# Monitor_strip_5050.net
KiCad netlist of a schematic drawn in EAGLE
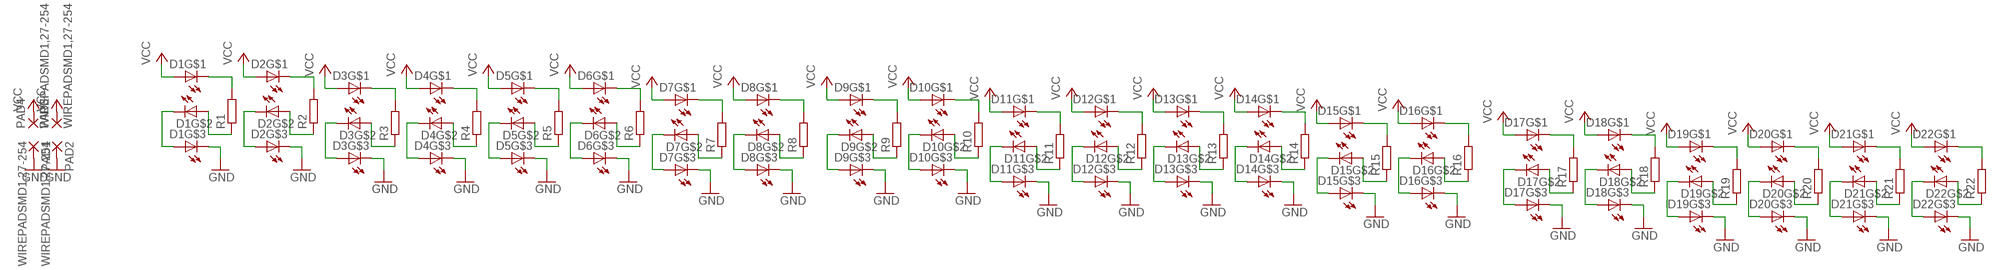
[diagram p0: schematic, sheet 1]

(export (version "E")
  (design (tool "Eeschema 10.0.6"))
  (components
    (comp (ref "D1")
      (value "LED5050_SEPARATES")
      (footprint "eagle-import:LED505_SMALLPADS")
      (libsource (lib "eagle-import") (part "LED5050_SEPARATES"))
    )
    (comp (ref "D2")
      (value "LED5050_SEPARATES")
      (footprint "eagle-import:LED505_SMALLPADS")
      (libsource (lib "eagle-import") (part "LED5050_SEPARATES"))
    )
    (comp (ref "D3")
      (value "LED5050_SEPARATES")
      (footprint "eagle-import:LED505_SMALLPADS")
      (libsource (lib "eagle-import") (part "LED5050_SEPARATES"))
    )
    (comp (ref "D4")
      (value "LED5050_SEPARATES")
      (footprint "eagle-import:LED505_SMALLPADS")
      (libsource (lib "eagle-import") (part "LED5050_SEPARATES"))
    )
    (comp (ref "D5")
      (value "LED5050_SEPARATES")
      (footprint "eagle-import:LED505_SMALLPADS")
      (libsource (lib "eagle-import") (part "LED5050_SEPARATES"))
    )
    (comp (ref "D6")
      (value "LED5050_SEPARATES")
      (footprint "eagle-import:LED505_SMALLPADS")
      (libsource (lib "eagle-import") (part "LED5050_SEPARATES"))
    )
    (comp (ref "D7")
      (value "LED5050_SEPARATES")
      (footprint "eagle-import:LED505_SMALLPADS")
      (libsource (lib "eagle-import") (part "LED5050_SEPARATES"))
    )
    (comp (ref "D8")
      (value "LED5050_SEPARATES")
      (footprint "eagle-import:LED505_SMALLPADS")
      (libsource (lib "eagle-import") (part "LED5050_SEPARATES"))
    )
    (comp (ref "D9")
      (value "LED5050_SEPARATES")
      (footprint "eagle-import:LED505_SMALLPADS")
      (libsource (lib "eagle-import") (part "LED5050_SEPARATES"))
    )
    (comp (ref "D10")
      (value "LED5050_SEPARATES")
      (footprint "eagle-import:LED505_SMALLPADS")
      (libsource (lib "eagle-import") (part "LED5050_SEPARATES"))
    )
    (comp (ref "D11")
      (value "LED5050_SEPARATES")
      (footprint "eagle-import:LED505_SMALLPADS")
      (libsource (lib "eagle-import") (part "LED5050_SEPARATES"))
    )
    (comp (ref "D12")
      (value "LED5050_SEPARATES")
      (footprint "eagle-import:LED505_SMALLPADS")
      (libsource (lib "eagle-import") (part "LED5050_SEPARATES"))
    )
    (comp (ref "D13")
      (value "LED5050_SEPARATES")
      (footprint "eagle-import:LED505_SMALLPADS")
      (libsource (lib "eagle-import") (part "LED5050_SEPARATES"))
    )
    (comp (ref "D14")
      (value "LED5050_SEPARATES")
      (footprint "eagle-import:LED505_SMALLPADS")
      (libsource (lib "eagle-import") (part "LED5050_SEPARATES"))
    )
    (comp (ref "D15")
      (value "LED5050_SEPARATES")
      (footprint "eagle-import:LED505_SMALLPADS")
      (libsource (lib "eagle-import") (part "LED5050_SEPARATES"))
    )
    (comp (ref "D16")
      (value "LED5050_SEPARATES")
      (footprint "eagle-import:LED505_SMALLPADS")
      (libsource (lib "eagle-import") (part "LED5050_SEPARATES"))
    )
    (comp (ref "D17")
      (value "LED5050_SEPARATES")
      (footprint "eagle-import:LED505_SMALLPADS")
      (libsource (lib "eagle-import") (part "LED5050_SEPARATES"))
    )
    (comp (ref "D18")
      (value "LED5050_SEPARATES")
      (footprint "eagle-import:LED505_SMALLPADS")
      (libsource (lib "eagle-import") (part "LED5050_SEPARATES"))
    )
    (comp (ref "D19")
      (value "LED5050_SEPARATES")
      (footprint "eagle-import:LED505_SMALLPADS")
      (libsource (lib "eagle-import") (part "LED5050_SEPARATES"))
    )
    (comp (ref "D20")
      (value "LED5050_SEPARATES")
      (footprint "eagle-import:LED505_SMALLPADS")
      (libsource (lib "eagle-import") (part "LED5050_SEPARATES"))
    )
    (comp (ref "D21")
      (value "LED5050_SEPARATES")
      (footprint "eagle-import:LED505_SMALLPADS")
      (libsource (lib "eagle-import") (part "LED5050_SEPARATES"))
    )
    (comp (ref "D22")
      (value "LED5050_SEPARATES")
      (footprint "eagle-import:LED505_SMALLPADS")
      (libsource (lib "eagle-import") (part "LED5050_SEPARATES"))
    )
    (comp (ref "PAD1")
      (value "WIREPADSMD1,27-254")
      (footprint "eagle-import:SMD1,27-2,54")
      (libsource (lib "eagle-import") (part "WIREPADSMD1,27-254"))
    )
    (comp (ref "PAD2")
      (value "WIREPADSMD1,27-254")
      (footprint "eagle-import:SMD1,27-2,54")
      (libsource (lib "eagle-import") (part "WIREPADSMD1,27-254"))
    )
    (comp (ref "PAD3")
      (value "WIREPADSMD1,27-254")
      (footprint "eagle-import:SMD1,27-2,54")
      (libsource (lib "eagle-import") (part "WIREPADSMD1,27-254"))
    )
    (comp (ref "PAD4")
      (value "WIREPADSMD1,27-254")
      (footprint "eagle-import:SMD1,27-2,54")
      (libsource (lib "eagle-import") (part "WIREPADSMD1,27-254"))
    )
    (comp (ref "R1")
      (value "R-EU_R0805")
      (footprint "eagle-import:R0805")
      (libsource (lib "eagle-import") (part "R-EU_R0805"))
    )
    (comp (ref "R2")
      (value "R-EU_R0805")
      (footprint "eagle-import:R0805")
      (libsource (lib "eagle-import") (part "R-EU_R0805"))
    )
    (comp (ref "R3")
      (value "R-EU_R0805")
      (footprint "eagle-import:R0805")
      (libsource (lib "eagle-import") (part "R-EU_R0805"))
    )
    (comp (ref "R4")
      (value "R-EU_R0805")
      (footprint "eagle-import:R0805")
      (libsource (lib "eagle-import") (part "R-EU_R0805"))
    )
    (comp (ref "R5")
      (value "R-EU_R0805")
      (footprint "eagle-import:R0805")
      (libsource (lib "eagle-import") (part "R-EU_R0805"))
    )
    (comp (ref "R6")
      (value "R-EU_R0805")
      (footprint "eagle-import:R0805")
      (libsource (lib "eagle-import") (part "R-EU_R0805"))
    )
    (comp (ref "R7")
      (value "R-EU_R0805")
      (footprint "eagle-import:R0805")
      (libsource (lib "eagle-import") (part "R-EU_R0805"))
    )
    (comp (ref "R8")
      (value "R-EU_R0805")
      (footprint "eagle-import:R0805")
      (libsource (lib "eagle-import") (part "R-EU_R0805"))
    )
    (comp (ref "R9")
      (value "R-EU_R0805")
      (footprint "eagle-import:R0805")
      (libsource (lib "eagle-import") (part "R-EU_R0805"))
    )
    (comp (ref "R10")
      (value "R-EU_R0805")
      (footprint "eagle-import:R0805")
      (libsource (lib "eagle-import") (part "R-EU_R0805"))
    )
    (comp (ref "R11")
      (value "R-EU_R0805")
      (footprint "eagle-import:R0805")
      (libsource (lib "eagle-import") (part "R-EU_R0805"))
    )
    (comp (ref "R12")
      (value "R-EU_R0805")
      (footprint "eagle-import:R0805")
      (libsource (lib "eagle-import") (part "R-EU_R0805"))
    )
    (comp (ref "R13")
      (value "R-EU_R0805")
      (footprint "eagle-import:R0805")
      (libsource (lib "eagle-import") (part "R-EU_R0805"))
    )
    (comp (ref "R14")
      (value "R-EU_R0805")
      (footprint "eagle-import:R0805")
      (libsource (lib "eagle-import") (part "R-EU_R0805"))
    )
    (comp (ref "R15")
      (value "R-EU_R0805")
      (footprint "eagle-import:R0805")
      (libsource (lib "eagle-import") (part "R-EU_R0805"))
    )
    (comp (ref "R16")
      (value "R-EU_R0805")
      (footprint "eagle-import:R0805")
      (libsource (lib "eagle-import") (part "R-EU_R0805"))
    )
    (comp (ref "R17")
      (value "R-EU_R0805")
      (footprint "eagle-import:R0805")
      (libsource (lib "eagle-import") (part "R-EU_R0805"))
    )
    (comp (ref "R18")
      (value "R-EU_R0805")
      (footprint "eagle-import:R0805")
      (libsource (lib "eagle-import") (part "R-EU_R0805"))
    )
    (comp (ref "R19")
      (value "R-EU_R0805")
      (footprint "eagle-import:R0805")
      (libsource (lib "eagle-import") (part "R-EU_R0805"))
    )
    (comp (ref "R20")
      (value "R-EU_R0805")
      (footprint "eagle-import:R0805")
      (libsource (lib "eagle-import") (part "R-EU_R0805"))
    )
    (comp (ref "R21")
      (value "R-EU_R0805")
      (footprint "eagle-import:R0805")
      (libsource (lib "eagle-import") (part "R-EU_R0805"))
    )
    (comp (ref "R22")
      (value "R-EU_R0805")
      (footprint "eagle-import:R0805")
      (libsource (lib "eagle-import") (part "R-EU_R0805"))
    )
  )
  (nets
    (net (code "1") (name "GND") (class "Default")
      (node (ref "D1") (pin "P$3") (pinfunction "C_P$3") (pintype "passive"))
      (node (ref "D10") (pin "P$3") (pinfunction "C_P$3") (pintype "passive"))
      (node (ref "D11") (pin "P$3") (pinfunction "C_P$3") (pintype "passive"))
      (node (ref "D12") (pin "P$3") (pinfunction "C_P$3") (pintype "passive"))
      (node (ref "D13") (pin "P$3") (pinfunction "C_P$3") (pintype "passive"))
      (node (ref "D14") (pin "P$3") (pinfunction "C_P$3") (pintype "passive"))
      (node (ref "D15") (pin "P$3") (pinfunction "C_P$3") (pintype "passive"))
      (node (ref "D16") (pin "P$3") (pinfunction "C_P$3") (pintype "passive"))
      (node (ref "D17") (pin "P$3") (pinfunction "C_P$3") (pintype "passive"))
      (node (ref "D18") (pin "P$3") (pinfunction "C_P$3") (pintype "passive"))
      (node (ref "D19") (pin "P$3") (pinfunction "C_P$3") (pintype "passive"))
      (node (ref "D2") (pin "P$3") (pinfunction "C_P$3") (pintype "passive"))
      (node (ref "D20") (pin "P$3") (pinfunction "C_P$3") (pintype "passive"))
      (node (ref "D21") (pin "P$3") (pinfunction "C_P$3") (pintype "passive"))
      (node (ref "D22") (pin "P$3") (pinfunction "C_P$3") (pintype "passive"))
      (node (ref "D3") (pin "P$3") (pinfunction "C_P$3") (pintype "passive"))
      (node (ref "D4") (pin "P$3") (pinfunction "C_P$3") (pintype "passive"))
      (node (ref "D5") (pin "P$3") (pinfunction "C_P$3") (pintype "passive"))
      (node (ref "D6") (pin "P$3") (pinfunction "C_P$3") (pintype "passive"))
      (node (ref "D7") (pin "P$3") (pinfunction "C_P$3") (pintype "passive"))
      (node (ref "D8") (pin "P$3") (pinfunction "C_P$3") (pintype "passive"))
      (node (ref "D9") (pin "P$3") (pinfunction "C_P$3") (pintype "passive"))
      (node (ref "PAD1") (pin "1") (pinfunction "P_1") (pintype "passive"))
      (node (ref "PAD2") (pin "1") (pinfunction "P_1") (pintype "passive"))
    )
    (net (code "2") (name "Net-(D1A-C)") (class "Default")
      (node (ref "D1") (pin "P$1") (pinfunction "C_P$1") (pintype "passive"))
      (node (ref "R1") (pin "2") (pinfunction "2_2") (pintype "passive"))
    )
    (net (code "3") (name "Net-(D1B-A)") (class "Default")
      (node (ref "D1") (pin "P$5") (pinfunction "A_P$5") (pintype "passive"))
      (node (ref "R1") (pin "1") (pinfunction "1_1") (pintype "passive"))
    )
    (net (code "4") (name "Net-(D1B-C)") (class "Default")
      (node (ref "D1") (pin "P$2") (pinfunction "C_P$2") (pintype "passive"))
      (node (ref "D1") (pin "P$4") (pinfunction "A_P$4") (pintype "passive"))
    )
    (net (code "5") (name "Net-(D2A-C)") (class "Default")
      (node (ref "D2") (pin "P$1") (pinfunction "C_P$1") (pintype "passive"))
      (node (ref "R2") (pin "2") (pinfunction "2_2") (pintype "passive"))
    )
    (net (code "6") (name "Net-(D2B-A)") (class "Default")
      (node (ref "D2") (pin "P$5") (pinfunction "A_P$5") (pintype "passive"))
      (node (ref "R2") (pin "1") (pinfunction "1_1") (pintype "passive"))
    )
    (net (code "7") (name "Net-(D2B-C)") (class "Default")
      (node (ref "D2") (pin "P$2") (pinfunction "C_P$2") (pintype "passive"))
      (node (ref "D2") (pin "P$4") (pinfunction "A_P$4") (pintype "passive"))
    )
    (net (code "8") (name "Net-(D3A-C)") (class "Default")
      (node (ref "D3") (pin "P$1") (pinfunction "C_P$1") (pintype "passive"))
      (node (ref "R3") (pin "2") (pinfunction "2_2") (pintype "passive"))
    )
    (net (code "9") (name "Net-(D3B-A)") (class "Default")
      (node (ref "D3") (pin "P$5") (pinfunction "A_P$5") (pintype "passive"))
      (node (ref "R3") (pin "1") (pinfunction "1_1") (pintype "passive"))
    )
    (net (code "10") (name "Net-(D3B-C)") (class "Default")
      (node (ref "D3") (pin "P$2") (pinfunction "C_P$2") (pintype "passive"))
      (node (ref "D3") (pin "P$4") (pinfunction "A_P$4") (pintype "passive"))
    )
    (net (code "11") (name "Net-(D4A-C)") (class "Default")
      (node (ref "D4") (pin "P$1") (pinfunction "C_P$1") (pintype "passive"))
      (node (ref "R4") (pin "2") (pinfunction "2_2") (pintype "passive"))
    )
    (net (code "12") (name "Net-(D4B-A)") (class "Default")
      (node (ref "D4") (pin "P$5") (pinfunction "A_P$5") (pintype "passive"))
      (node (ref "R4") (pin "1") (pinfunction "1_1") (pintype "passive"))
    )
    (net (code "13") (name "Net-(D4B-C)") (class "Default")
      (node (ref "D4") (pin "P$2") (pinfunction "C_P$2") (pintype "passive"))
      (node (ref "D4") (pin "P$4") (pinfunction "A_P$4") (pintype "passive"))
    )
    (net (code "14") (name "Net-(D5A-C)") (class "Default")
      (node (ref "D5") (pin "P$1") (pinfunction "C_P$1") (pintype "passive"))
      (node (ref "R5") (pin "2") (pinfunction "2_2") (pintype "passive"))
    )
    (net (code "15") (name "Net-(D5B-A)") (class "Default")
      (node (ref "D5") (pin "P$5") (pinfunction "A_P$5") (pintype "passive"))
      (node (ref "R5") (pin "1") (pinfunction "1_1") (pintype "passive"))
    )
    (net (code "16") (name "Net-(D5B-C)") (class "Default")
      (node (ref "D5") (pin "P$2") (pinfunction "C_P$2") (pintype "passive"))
      (node (ref "D5") (pin "P$4") (pinfunction "A_P$4") (pintype "passive"))
    )
    (net (code "17") (name "Net-(D6A-C)") (class "Default")
      (node (ref "D6") (pin "P$1") (pinfunction "C_P$1") (pintype "passive"))
      (node (ref "R6") (pin "2") (pinfunction "2_2") (pintype "passive"))
    )
    (net (code "18") (name "Net-(D6B-A)") (class "Default")
      (node (ref "D6") (pin "P$5") (pinfunction "A_P$5") (pintype "passive"))
      (node (ref "R6") (pin "1") (pinfunction "1_1") (pintype "passive"))
    )
    (net (code "19") (name "Net-(D6B-C)") (class "Default")
      (node (ref "D6") (pin "P$2") (pinfunction "C_P$2") (pintype "passive"))
      (node (ref "D6") (pin "P$4") (pinfunction "A_P$4") (pintype "passive"))
    )
    (net (code "20") (name "Net-(D7A-C)") (class "Default")
      (node (ref "D7") (pin "P$1") (pinfunction "C_P$1") (pintype "passive"))
      (node (ref "R7") (pin "2") (pinfunction "2_2") (pintype "passive"))
    )
    (net (code "21") (name "Net-(D7B-A)") (class "Default")
      (node (ref "D7") (pin "P$5") (pinfunction "A_P$5") (pintype "passive"))
      (node (ref "R7") (pin "1") (pinfunction "1_1") (pintype "passive"))
    )
    (net (code "22") (name "Net-(D7B-C)") (class "Default")
      (node (ref "D7") (pin "P$2") (pinfunction "C_P$2") (pintype "passive"))
      (node (ref "D7") (pin "P$4") (pinfunction "A_P$4") (pintype "passive"))
    )
    (net (code "23") (name "Net-(D8A-C)") (class "Default")
      (node (ref "D8") (pin "P$1") (pinfunction "C_P$1") (pintype "passive"))
      (node (ref "R8") (pin "2") (pinfunction "2_2") (pintype "passive"))
    )
    (net (code "24") (name "Net-(D8B-A)") (class "Default")
      (node (ref "D8") (pin "P$5") (pinfunction "A_P$5") (pintype "passive"))
      (node (ref "R8") (pin "1") (pinfunction "1_1") (pintype "passive"))
    )
    (net (code "25") (name "Net-(D8B-C)") (class "Default")
      (node (ref "D8") (pin "P$2") (pinfunction "C_P$2") (pintype "passive"))
      (node (ref "D8") (pin "P$4") (pinfunction "A_P$4") (pintype "passive"))
    )
    (net (code "26") (name "Net-(D9A-C)") (class "Default")
      (node (ref "D9") (pin "P$1") (pinfunction "C_P$1") (pintype "passive"))
      (node (ref "R9") (pin "2") (pinfunction "2_2") (pintype "passive"))
    )
    (net (code "27") (name "Net-(D9B-A)") (class "Default")
      (node (ref "D9") (pin "P$5") (pinfunction "A_P$5") (pintype "passive"))
      (node (ref "R9") (pin "1") (pinfunction "1_1") (pintype "passive"))
    )
    (net (code "28") (name "Net-(D9B-C)") (class "Default")
      (node (ref "D9") (pin "P$2") (pinfunction "C_P$2") (pintype "passive"))
      (node (ref "D9") (pin "P$4") (pinfunction "A_P$4") (pintype "passive"))
    )
    (net (code "29") (name "Net-(D10A-C)") (class "Default")
      (node (ref "D10") (pin "P$1") (pinfunction "C_P$1") (pintype "passive"))
      (node (ref "R10") (pin "2") (pinfunction "2_2") (pintype "passive"))
    )
    (net (code "30") (name "Net-(D10B-A)") (class "Default")
      (node (ref "D10") (pin "P$5") (pinfunction "A_P$5") (pintype "passive"))
      (node (ref "R10") (pin "1") (pinfunction "1_1") (pintype "passive"))
    )
    (net (code "31") (name "Net-(D10B-C)") (class "Default")
      (node (ref "D10") (pin "P$2") (pinfunction "C_P$2") (pintype "passive"))
      (node (ref "D10") (pin "P$4") (pinfunction "A_P$4") (pintype "passive"))
    )
    (net (code "32") (name "Net-(D11A-C)") (class "Default")
      (node (ref "D11") (pin "P$1") (pinfunction "C_P$1") (pintype "passive"))
      (node (ref "R11") (pin "2") (pinfunction "2_2") (pintype "passive"))
    )
    (net (code "33") (name "Net-(D11B-A)") (class "Default")
      (node (ref "D11") (pin "P$5") (pinfunction "A_P$5") (pintype "passive"))
      (node (ref "R11") (pin "1") (pinfunction "1_1") (pintype "passive"))
    )
    (net (code "34") (name "Net-(D11B-C)") (class "Default")
      (node (ref "D11") (pin "P$2") (pinfunction "C_P$2") (pintype "passive"))
      (node (ref "D11") (pin "P$4") (pinfunction "A_P$4") (pintype "passive"))
    )
    (net (code "35") (name "Net-(D12A-C)") (class "Default")
      (node (ref "D12") (pin "P$1") (pinfunction "C_P$1") (pintype "passive"))
      (node (ref "R12") (pin "2") (pinfunction "2_2") (pintype "passive"))
    )
    (net (code "36") (name "Net-(D12B-A)") (class "Default")
      (node (ref "D12") (pin "P$5") (pinfunction "A_P$5") (pintype "passive"))
      (node (ref "R12") (pin "1") (pinfunction "1_1") (pintype "passive"))
    )
    (net (code "37") (name "Net-(D12B-C)") (class "Default")
      (node (ref "D12") (pin "P$2") (pinfunction "C_P$2") (pintype "passive"))
      (node (ref "D12") (pin "P$4") (pinfunction "A_P$4") (pintype "passive"))
    )
    (net (code "38") (name "Net-(D13A-C)") (class "Default")
      (node (ref "D13") (pin "P$1") (pinfunction "C_P$1") (pintype "passive"))
      (node (ref "R13") (pin "2") (pinfunction "2_2") (pintype "passive"))
    )
    (net (code "39") (name "Net-(D13B-A)") (class "Default")
      (node (ref "D13") (pin "P$5") (pinfunction "A_P$5") (pintype "passive"))
      (node (ref "R13") (pin "1") (pinfunction "1_1") (pintype "passive"))
    )
    (net (code "40") (name "Net-(D13B-C)") (class "Default")
      (node (ref "D13") (pin "P$2") (pinfunction "C_P$2") (pintype "passive"))
      (node (ref "D13") (pin "P$4") (pinfunction "A_P$4") (pintype "passive"))
    )
    (net (code "41") (name "Net-(D14A-C)") (class "Default")
      (node (ref "D14") (pin "P$1") (pinfunction "C_P$1") (pintype "passive"))
      (node (ref "R14") (pin "2") (pinfunction "2_2") (pintype "passive"))
    )
    (net (code "42") (name "Net-(D14B-A)") (class "Default")
      (node (ref "D14") (pin "P$5") (pinfunction "A_P$5") (pintype "passive"))
      (node (ref "R14") (pin "1") (pinfunction "1_1") (pintype "passive"))
    )
    (net (code "43") (name "Net-(D14B-C)") (class "Default")
      (node (ref "D14") (pin "P$2") (pinfunction "C_P$2") (pintype "passive"))
      (node (ref "D14") (pin "P$4") (pinfunction "A_P$4") (pintype "passive"))
    )
    (net (code "44") (name "Net-(D15A-C)") (class "Default")
      (node (ref "D15") (pin "P$1") (pinfunction "C_P$1") (pintype "passive"))
      (node (ref "R15") (pin "2") (pinfunction "2_2") (pintype "passive"))
    )
    (net (code "45") (name "Net-(D15B-A)") (class "Default")
      (node (ref "D15") (pin "P$5") (pinfunction "A_P$5") (pintype "passive"))
      (node (ref "R15") (pin "1") (pinfunction "1_1") (pintype "passive"))
    )
    (net (code "46") (name "Net-(D15B-C)") (class "Default")
      (node (ref "D15") (pin "P$2") (pinfunction "C_P$2") (pintype "passive"))
      (node (ref "D15") (pin "P$4") (pinfunction "A_P$4") (pintype "passive"))
    )
    (net (code "47") (name "Net-(D16A-C)") (class "Default")
      (node (ref "D16") (pin "P$1") (pinfunction "C_P$1") (pintype "passive"))
      (node (ref "R16") (pin "2") (pinfunction "2_2") (pintype "passive"))
    )
    (net (code "48") (name "Net-(D16B-A)") (class "Default")
      (node (ref "D16") (pin "P$5") (pinfunction "A_P$5") (pintype "passive"))
      (node (ref "R16") (pin "1") (pinfunction "1_1") (pintype "passive"))
    )
    (net (code "49") (name "Net-(D16B-C)") (class "Default")
      (node (ref "D16") (pin "P$2") (pinfunction "C_P$2") (pintype "passive"))
      (node (ref "D16") (pin "P$4") (pinfunction "A_P$4") (pintype "passive"))
    )
    (net (code "50") (name "Net-(D17A-C)") (class "Default")
      (node (ref "D17") (pin "P$1") (pinfunction "C_P$1") (pintype "passive"))
      (node (ref "R17") (pin "2") (pinfunction "2_2") (pintype "passive"))
    )
    (net (code "51") (name "Net-(D17B-A)") (class "Default")
      (node (ref "D17") (pin "P$5") (pinfunction "A_P$5") (pintype "passive"))
      (node (ref "R17") (pin "1") (pinfunction "1_1") (pintype "passive"))
    )
    (net (code "52") (name "Net-(D17B-C)") (class "Default")
      (node (ref "D17") (pin "P$2") (pinfunction "C_P$2") (pintype "passive"))
      (node (ref "D17") (pin "P$4") (pinfunction "A_P$4") (pintype "passive"))
    )
    (net (code "53") (name "Net-(D18A-C)") (class "Default")
      (node (ref "D18") (pin "P$1") (pinfunction "C_P$1") (pintype "passive"))
      (node (ref "R18") (pin "2") (pinfunction "2_2") (pintype "passive"))
    )
    (net (code "54") (name "Net-(D18B-A)") (class "Default")
      (node (ref "D18") (pin "P$5") (pinfunction "A_P$5") (pintype "passive"))
      (node (ref "R18") (pin "1") (pinfunction "1_1") (pintype "passive"))
    )
    (net (code "55") (name "Net-(D18B-C)") (class "Default")
      (node (ref "D18") (pin "P$2") (pinfunction "C_P$2") (pintype "passive"))
      (node (ref "D18") (pin "P$4") (pinfunction "A_P$4") (pintype "passive"))
    )
    (net (code "56") (name "Net-(D19A-C)") (class "Default")
      (node (ref "D19") (pin "P$1") (pinfunction "C_P$1") (pintype "passive"))
      (node (ref "R19") (pin "2") (pinfunction "2_2") (pintype "passive"))
    )
    (net (code "57") (name "Net-(D19B-A)") (class "Default")
      (node (ref "D19") (pin "P$5") (pinfunction "A_P$5") (pintype "passive"))
      (node (ref "R19") (pin "1") (pinfunction "1_1") (pintype "passive"))
    )
    (net (code "58") (name "Net-(D19B-C)") (class "Default")
      (node (ref "D19") (pin "P$2") (pinfunction "C_P$2") (pintype "passive"))
      (node (ref "D19") (pin "P$4") (pinfunction "A_P$4") (pintype "passive"))
    )
    (net (code "59") (name "Net-(D20A-C)") (class "Default")
      (node (ref "D20") (pin "P$1") (pinfunction "C_P$1") (pintype "passive"))
      (node (ref "R20") (pin "2") (pinfunction "2_2") (pintype "passive"))
    )
    (net (code "60") (name "Net-(D20B-A)") (class "Default")
      (node (ref "D20") (pin "P$5") (pinfunction "A_P$5") (pintype "passive"))
      (node (ref "R20") (pin "1") (pinfunction "1_1") (pintype "passive"))
    )
    (net (code "61") (name "Net-(D20B-C)") (class "Default")
      (node (ref "D20") (pin "P$2") (pinfunction "C_P$2") (pintype "passive"))
      (node (ref "D20") (pin "P$4") (pinfunction "A_P$4") (pintype "passive"))
    )
    (net (code "62") (name "Net-(D21A-C)") (class "Default")
      (node (ref "D21") (pin "P$1") (pinfunction "C_P$1") (pintype "passive"))
      (node (ref "R21") (pin "2") (pinfunction "2_2") (pintype "passive"))
    )
    (net (code "63") (name "Net-(D21B-A)") (class "Default")
      (node (ref "D21") (pin "P$5") (pinfunction "A_P$5") (pintype "passive"))
      (node (ref "R21") (pin "1") (pinfunction "1_1") (pintype "passive"))
    )
    (net (code "64") (name "Net-(D21B-C)") (class "Default")
      (node (ref "D21") (pin "P$2") (pinfunction "C_P$2") (pintype "passive"))
      (node (ref "D21") (pin "P$4") (pinfunction "A_P$4") (pintype "passive"))
    )
    (net (code "65") (name "Net-(D22A-C)") (class "Default")
      (node (ref "D22") (pin "P$1") (pinfunction "C_P$1") (pintype "passive"))
      (node (ref "R22") (pin "2") (pinfunction "2_2") (pintype "passive"))
    )
    (net (code "66") (name "Net-(D22B-A)") (class "Default")
      (node (ref "D22") (pin "P$5") (pinfunction "A_P$5") (pintype "passive"))
      (node (ref "R22") (pin "1") (pinfunction "1_1") (pintype "passive"))
    )
    (net (code "67") (name "Net-(D22B-C)") (class "Default")
      (node (ref "D22") (pin "P$2") (pinfunction "C_P$2") (pintype "passive"))
      (node (ref "D22") (pin "P$4") (pinfunction "A_P$4") (pintype "passive"))
    )
    (net (code "68") (name "VCC") (class "Default")
      (node (ref "D1") (pin "P$6") (pinfunction "A_P$6") (pintype "passive"))
      (node (ref "D10") (pin "P$6") (pinfunction "A_P$6") (pintype "passive"))
      (node (ref "D11") (pin "P$6") (pinfunction "A_P$6") (pintype "passive"))
      (node (ref "D12") (pin "P$6") (pinfunction "A_P$6") (pintype "passive"))
      (node (ref "D13") (pin "P$6") (pinfunction "A_P$6") (pintype "passive"))
      (node (ref "D14") (pin "P$6") (pinfunction "A_P$6") (pintype "passive"))
      (node (ref "D15") (pin "P$6") (pinfunction "A_P$6") (pintype "passive"))
      (node (ref "D16") (pin "P$6") (pinfunction "A_P$6") (pintype "passive"))
      (node (ref "D17") (pin "P$6") (pinfunction "A_P$6") (pintype "passive"))
      (node (ref "D18") (pin "P$6") (pinfunction "A_P$6") (pintype "passive"))
      (node (ref "D19") (pin "P$6") (pinfunction "A_P$6") (pintype "passive"))
      (node (ref "D2") (pin "P$6") (pinfunction "A_P$6") (pintype "passive"))
      (node (ref "D20") (pin "P$6") (pinfunction "A_P$6") (pintype "passive"))
      (node (ref "D21") (pin "P$6") (pinfunction "A_P$6") (pintype "passive"))
      (node (ref "D22") (pin "P$6") (pinfunction "A_P$6") (pintype "passive"))
      (node (ref "D3") (pin "P$6") (pinfunction "A_P$6") (pintype "passive"))
      (node (ref "D4") (pin "P$6") (pinfunction "A_P$6") (pintype "passive"))
      (node (ref "D5") (pin "P$6") (pinfunction "A_P$6") (pintype "passive"))
      (node (ref "D6") (pin "P$6") (pinfunction "A_P$6") (pintype "passive"))
      (node (ref "D7") (pin "P$6") (pinfunction "A_P$6") (pintype "passive"))
      (node (ref "D8") (pin "P$6") (pinfunction "A_P$6") (pintype "passive"))
      (node (ref "D9") (pin "P$6") (pinfunction "A_P$6") (pintype "passive"))
      (node (ref "PAD3") (pin "1") (pinfunction "P_1") (pintype "passive"))
      (node (ref "PAD4") (pin "1") (pinfunction "P_1") (pintype "passive"))
    )
  )
)
